# FMC_SINGLE_LPC_BREAKOUT.net
KiCad netlist of a schematic drawn in Altium Designer
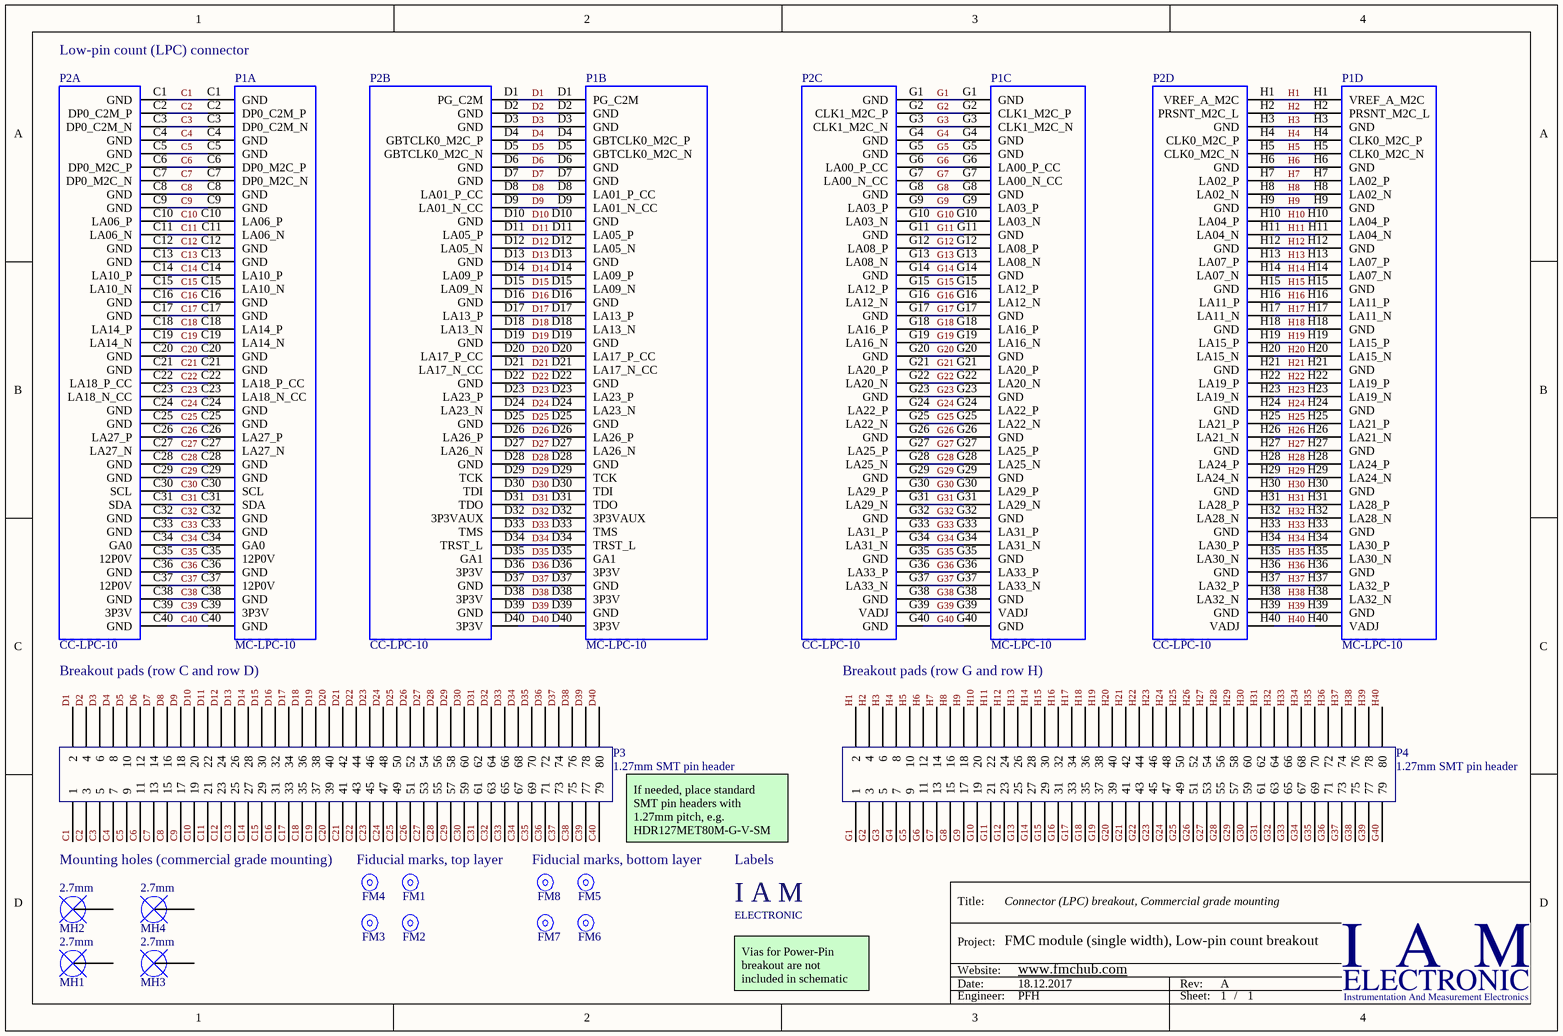
[diagram p0: FMC_SINGLE_LPC_BREAKOUT.SchDoc]

(export (version "E")
  (design (tool "Eeschema 10.0.6"))
  (components
    (comp (ref "FM1")
      (value "1mm")
      (footprint "FIDUCIAL_MARK_ROUND")
      (description "Fiducial mark, width 1mm, clearance 3mm")
      (libsource (lib "VITA_57_FMC") (part "Fiducial_Mark"))
    )
    (comp (ref "FM2")
      (value "1mm")
      (footprint "FIDUCIAL_MARK_ROUND")
      (description "Fiducial mark, width 1mm, clearance 3mm")
      (libsource (lib "VITA_57_FMC") (part "Fiducial_Mark"))
    )
    (comp (ref "FM3")
      (value "1mm")
      (footprint "FIDUCIAL_MARK_ROUND")
      (description "Fiducial mark, width 1mm, clearance 3mm")
      (libsource (lib "VITA_57_FMC") (part "Fiducial_Mark"))
    )
    (comp (ref "FM4")
      (value "1mm")
      (footprint "FIDUCIAL_MARK_ROUND")
      (description "Fiducial mark, width 1mm, clearance 3mm")
      (libsource (lib "VITA_57_FMC") (part "Fiducial_Mark"))
    )
    (comp (ref "FM5")
      (value "1mm")
      (footprint "FIDUCIAL_MARK_ROUND")
      (description "Fiducial mark, width 1mm, clearance 3mm")
      (libsource (lib "VITA_57_FMC") (part "Fiducial_Mark"))
    )
    (comp (ref "FM6")
      (value "1mm")
      (footprint "FIDUCIAL_MARK_ROUND")
      (description "Fiducial mark, width 1mm, clearance 3mm")
      (libsource (lib "VITA_57_FMC") (part "Fiducial_Mark"))
    )
    (comp (ref "FM7")
      (value "1mm")
      (footprint "FIDUCIAL_MARK_ROUND")
      (description "Fiducial mark, width 1mm, clearance 3mm")
      (libsource (lib "VITA_57_FMC") (part "Fiducial_Mark"))
    )
    (comp (ref "FM8")
      (value "1mm")
      (footprint "FIDUCIAL_MARK_ROUND")
      (description "Fiducial mark, width 1mm, clearance 3mm")
      (libsource (lib "VITA_57_FMC") (part "Fiducial_Mark"))
    )
    (comp (ref "MH1")
      (value "2.7mm")
      (footprint "Mounting_Hole_Plated_2.7mm - d3.1mm")
      (description "Mounting hole, hole size 2.7mm")
      (libsource (lib "VITA_57_FMC") (part "Mounting_Hole_2.7mm"))
    )
    (comp (ref "MH2")
      (value "2.7mm")
      (footprint "Mounting_Hole_Plated_2.7mm - d3.1mm")
      (description "Mounting hole, hole size 2.7mm")
      (libsource (lib "VITA_57_FMC") (part "Mounting_Hole_2.7mm"))
    )
    (comp (ref "MH3")
      (value "2.7mm")
      (footprint "Mounting_Hole_Plated_2.7mm-COVERED")
      (description "Mounting hole, hole size 2.7mm")
      (libsource (lib "VITA_57_FMC") (part "Mounting_Hole_2.7mm"))
    )
    (comp (ref "MH4")
      (value "2.7mm")
      (footprint "Mounting_Hole_Plated_2.7mm-COVERED")
      (description "Mounting hole, hole size 2.7mm")
      (libsource (lib "VITA_57_FMC") (part "Mounting_Hole_2.7mm"))
    )
    (comp (ref "P1")
      (value "MC-LPC-10")
      (footprint "ASP-134604-01")
      (description "MC-LPC-10, FMC Low-pin count connector, lead free, 160 I/Os, male, 10 mm mated stack height")
      (fields (field (name "MANUFACTURER") "Samtec") (field (name "PART") "ASP-134604-01"))
      (libsource (lib "VITA_57_FMC") (part "MC-LPC-10"))
    )
    (comp (ref "P2")
      (value "CC-LPC-10")
      (footprint "ASP-134603-01")
      (description "CC-LPC-10, FMC Low-pin count connector, lead free, 160 I/Os, female, 10 mm mated stack height")
      (fields (field (name "MANUFACTURER") "Samtec") (field (name "PART") "ASP-134603-01"))
      (libsource (lib "VITA_57_FMC") (part "CC-LPC-10"))
    )
    (comp (ref "P3")
      (value "1.27mm SMT pin header")
      (footprint "FTS-140-01-L-DV-A")
      (description "1.27 MM 80 PIN VERTICAL MALE HEADER")
      (fields (field (name "PART") "HDR127MET80M-G-V-SM") (field (name "MANUFACTURER") "Chip Quik Inc."))
      (libsource (lib "FTS-140") (part "FTS-140-X-DV"))
    )
    (comp (ref "P4")
      (value "1.27mm SMT pin header")
      (footprint "FTS-140-01-L-DV-A")
      (description "1.27 MM 80 PIN VERTICAL MALE HEADER")
      (fields (field (name "PART") "HDR127MET80M-G-V-SM") (field (name "MANUFACTURER") "Chip Quik Inc."))
      (libsource (lib "FTS-140") (part "FTS-140-X-DV"))
    )
    (comp (ref "STR1")
      (value "IAM LOGO")
      (footprint "IAM LOGO - MEDIUM")
      (description "I A M E L E C T R O N I C - Logo")
      (fields (field (name "MANUFACTURER") "IAM ELECTRONIC") (field (name "PART") "Logo"))
      (libsource (lib "IAM_LOGOS") (part "IAM_LOGO"))
    )
  )
  (nets
    (net (code "1") (name "/C1") (class "Default")
      (node (ref "P1") (pin "C1") (pinfunction "GND_C1") (pintype "passive"))
      (node (ref "P2") (pin "C1") (pinfunction "GND_C1") (pintype "passive"))
      (node (ref "P3") (pin "1") (pinfunction "1_1") (pintype "passive"))
    )
    (net (code "2") (name "/C2") (class "Default")
      (node (ref "P1") (pin "C2") (pinfunction "DP0_C2M_P_C2") (pintype "passive"))
      (node (ref "P2") (pin "C2") (pinfunction "DP0_C2M_P_C2") (pintype "passive"))
      (node (ref "P3") (pin "3") (pinfunction "3_3") (pintype "passive"))
    )
    (net (code "3") (name "/C3") (class "Default")
      (node (ref "P1") (pin "C3") (pinfunction "DP0_C2M_N_C3") (pintype "passive"))
      (node (ref "P2") (pin "C3") (pinfunction "DP0_C2M_N_C3") (pintype "passive"))
      (node (ref "P3") (pin "5") (pinfunction "5_5") (pintype "passive"))
    )
    (net (code "4") (name "/C4") (class "Default")
      (node (ref "P1") (pin "C4") (pinfunction "GND_C4") (pintype "passive"))
      (node (ref "P2") (pin "C4") (pinfunction "GND_C4") (pintype "passive"))
      (node (ref "P3") (pin "7") (pinfunction "7_7") (pintype "passive"))
    )
    (net (code "5") (name "/C5") (class "Default")
      (node (ref "P1") (pin "C5") (pinfunction "GND_C5") (pintype "passive"))
      (node (ref "P2") (pin "C5") (pinfunction "GND_C5") (pintype "passive"))
      (node (ref "P3") (pin "9") (pinfunction "9_9") (pintype "passive"))
    )
    (net (code "6") (name "/C6") (class "Default")
      (node (ref "P1") (pin "C6") (pinfunction "DP0_M2C_P_C6") (pintype "passive"))
      (node (ref "P2") (pin "C6") (pinfunction "DP0_M2C_P_C6") (pintype "passive"))
      (node (ref "P3") (pin "11") (pinfunction "11_11") (pintype "passive"))
    )
    (net (code "7") (name "/C7") (class "Default")
      (node (ref "P1") (pin "C7") (pinfunction "DP0_M2C_N_C7") (pintype "passive"))
      (node (ref "P2") (pin "C7") (pinfunction "DP0_M2C_N_C7") (pintype "passive"))
      (node (ref "P3") (pin "13") (pinfunction "13_13") (pintype "passive"))
    )
    (net (code "8") (name "/C8") (class "Default")
      (node (ref "P1") (pin "C8") (pinfunction "GND_C8") (pintype "passive"))
      (node (ref "P2") (pin "C8") (pinfunction "GND_C8") (pintype "passive"))
      (node (ref "P3") (pin "15") (pinfunction "15_15") (pintype "passive"))
    )
    (net (code "9") (name "/C9") (class "Default")
      (node (ref "P1") (pin "C9") (pinfunction "GND_C9") (pintype "passive"))
      (node (ref "P2") (pin "C9") (pinfunction "GND_C9") (pintype "passive"))
      (node (ref "P3") (pin "17") (pinfunction "17_17") (pintype "passive"))
    )
    (net (code "10") (name "/C10") (class "Default")
      (node (ref "P1") (pin "C10") (pinfunction "LA06_P_C10") (pintype "passive"))
      (node (ref "P2") (pin "C10") (pinfunction "LA06_P_C10") (pintype "passive"))
      (node (ref "P3") (pin "19") (pinfunction "19_19") (pintype "passive"))
    )
    (net (code "11") (name "/C11") (class "Default")
      (node (ref "P1") (pin "C11") (pinfunction "LA06_N_C11") (pintype "passive"))
      (node (ref "P2") (pin "C11") (pinfunction "LA06_N_C11") (pintype "passive"))
      (node (ref "P3") (pin "21") (pinfunction "21_21") (pintype "passive"))
    )
    (net (code "12") (name "/C12") (class "Default")
      (node (ref "P1") (pin "C12") (pinfunction "GND_C12") (pintype "passive"))
      (node (ref "P2") (pin "C12") (pinfunction "GND_C12") (pintype "passive"))
      (node (ref "P3") (pin "23") (pinfunction "23_23") (pintype "passive"))
    )
    (net (code "13") (name "/C13") (class "Default")
      (node (ref "P1") (pin "C13") (pinfunction "GND_C13") (pintype "passive"))
      (node (ref "P2") (pin "C13") (pinfunction "GND_C13") (pintype "passive"))
      (node (ref "P3") (pin "25") (pinfunction "25_25") (pintype "passive"))
    )
    (net (code "14") (name "/C14") (class "Default")
      (node (ref "P1") (pin "C14") (pinfunction "LA10_P_C14") (pintype "passive"))
      (node (ref "P2") (pin "C14") (pinfunction "LA10_P_C14") (pintype "passive"))
      (node (ref "P3") (pin "27") (pinfunction "27_27") (pintype "passive"))
    )
    (net (code "15") (name "/C15") (class "Default")
      (node (ref "P1") (pin "C15") (pinfunction "LA10_N_C15") (pintype "passive"))
      (node (ref "P2") (pin "C15") (pinfunction "LA10_N_C15") (pintype "passive"))
      (node (ref "P3") (pin "29") (pinfunction "29_29") (pintype "passive"))
    )
    (net (code "16") (name "/C16") (class "Default")
      (node (ref "P1") (pin "C16") (pinfunction "GND_C16") (pintype "passive"))
      (node (ref "P2") (pin "C16") (pinfunction "GND_C16") (pintype "passive"))
      (node (ref "P3") (pin "31") (pinfunction "31_31") (pintype "passive"))
    )
    (net (code "17") (name "/C17") (class "Default")
      (node (ref "P1") (pin "C17") (pinfunction "GND_C17") (pintype "passive"))
      (node (ref "P2") (pin "C17") (pinfunction "GND_C17") (pintype "passive"))
      (node (ref "P3") (pin "33") (pinfunction "33_33") (pintype "passive"))
    )
    (net (code "18") (name "/C18") (class "Default")
      (node (ref "P1") (pin "C18") (pinfunction "LA14_P_C18") (pintype "passive"))
      (node (ref "P2") (pin "C18") (pinfunction "LA14_P_C18") (pintype "passive"))
      (node (ref "P3") (pin "35") (pinfunction "35_35") (pintype "passive"))
    )
    (net (code "19") (name "/C19") (class "Default")
      (node (ref "P1") (pin "C19") (pinfunction "LA14_N_C19") (pintype "passive"))
      (node (ref "P2") (pin "C19") (pinfunction "LA14_N_C19") (pintype "passive"))
      (node (ref "P3") (pin "37") (pinfunction "37_37") (pintype "passive"))
    )
    (net (code "20") (name "/C20") (class "Default")
      (node (ref "P1") (pin "C20") (pinfunction "GND_C20") (pintype "passive"))
      (node (ref "P2") (pin "C20") (pinfunction "GND_C20") (pintype "passive"))
      (node (ref "P3") (pin "39") (pinfunction "39_39") (pintype "passive"))
    )
    (net (code "21") (name "/C21") (class "Default")
      (node (ref "P1") (pin "C21") (pinfunction "GND_C21") (pintype "passive"))
      (node (ref "P2") (pin "C21") (pinfunction "GND_C21") (pintype "passive"))
      (node (ref "P3") (pin "41") (pinfunction "41_41") (pintype "passive"))
    )
    (net (code "22") (name "/C22") (class "Default")
      (node (ref "P1") (pin "C22") (pinfunction "LA18_P_CC_C22") (pintype "passive"))
      (node (ref "P2") (pin "C22") (pinfunction "LA18_P_CC_C22") (pintype "passive"))
      (node (ref "P3") (pin "43") (pinfunction "43_43") (pintype "passive"))
    )
    (net (code "23") (name "/C23") (class "Default")
      (node (ref "P1") (pin "C23") (pinfunction "LA18_N_CC_C23") (pintype "passive"))
      (node (ref "P2") (pin "C23") (pinfunction "LA18_N_CC_C23") (pintype "passive"))
      (node (ref "P3") (pin "45") (pinfunction "45_45") (pintype "passive"))
    )
    (net (code "24") (name "/C24") (class "Default")
      (node (ref "P1") (pin "C24") (pinfunction "GND_C24") (pintype "passive"))
      (node (ref "P2") (pin "C24") (pinfunction "GND_C24") (pintype "passive"))
      (node (ref "P3") (pin "47") (pinfunction "47_47") (pintype "passive"))
    )
    (net (code "25") (name "/C25") (class "Default")
      (node (ref "P1") (pin "C25") (pinfunction "GND_C25") (pintype "passive"))
      (node (ref "P2") (pin "C25") (pinfunction "GND_C25") (pintype "passive"))
      (node (ref "P3") (pin "49") (pinfunction "49_49") (pintype "passive"))
    )
    (net (code "26") (name "/C26") (class "Default")
      (node (ref "P1") (pin "C26") (pinfunction "LA27_P_C26") (pintype "passive"))
      (node (ref "P2") (pin "C26") (pinfunction "LA27_P_C26") (pintype "passive"))
      (node (ref "P3") (pin "51") (pinfunction "51_51") (pintype "passive"))
    )
    (net (code "27") (name "/C27") (class "Default")
      (node (ref "P1") (pin "C27") (pinfunction "LA27_N_C27") (pintype "passive"))
      (node (ref "P2") (pin "C27") (pinfunction "LA27_N_C27") (pintype "passive"))
      (node (ref "P3") (pin "53") (pinfunction "53_53") (pintype "passive"))
    )
    (net (code "28") (name "/C28") (class "Default")
      (node (ref "P1") (pin "C28") (pinfunction "GND_C28") (pintype "passive"))
      (node (ref "P2") (pin "C28") (pinfunction "GND_C28") (pintype "passive"))
      (node (ref "P3") (pin "55") (pinfunction "55_55") (pintype "passive"))
    )
    (net (code "29") (name "/C29") (class "Default")
      (node (ref "P1") (pin "C29") (pinfunction "GND_C29") (pintype "passive"))
      (node (ref "P2") (pin "C29") (pinfunction "GND_C29") (pintype "passive"))
      (node (ref "P3") (pin "57") (pinfunction "57_57") (pintype "passive"))
    )
    (net (code "30") (name "/C30") (class "Default")
      (node (ref "P1") (pin "C30") (pinfunction "SCL_C30") (pintype "passive"))
      (node (ref "P2") (pin "C30") (pinfunction "SCL_C30") (pintype "passive"))
      (node (ref "P3") (pin "59") (pinfunction "59_59") (pintype "passive"))
    )
    (net (code "31") (name "/C31") (class "Default")
      (node (ref "P1") (pin "C31") (pinfunction "SDA_C31") (pintype "passive"))
      (node (ref "P2") (pin "C31") (pinfunction "SDA_C31") (pintype "passive"))
      (node (ref "P3") (pin "61") (pinfunction "61_61") (pintype "passive"))
    )
    (net (code "32") (name "/C32") (class "Default")
      (node (ref "P1") (pin "C32") (pinfunction "GND_C32") (pintype "passive"))
      (node (ref "P2") (pin "C32") (pinfunction "GND_C32") (pintype "passive"))
      (node (ref "P3") (pin "63") (pinfunction "63_63") (pintype "passive"))
    )
    (net (code "33") (name "/C33") (class "Default")
      (node (ref "P1") (pin "C33") (pinfunction "GND_C33") (pintype "passive"))
      (node (ref "P2") (pin "C33") (pinfunction "GND_C33") (pintype "passive"))
      (node (ref "P3") (pin "65") (pinfunction "65_65") (pintype "passive"))
    )
    (net (code "34") (name "/C34") (class "Default")
      (node (ref "P1") (pin "C34") (pinfunction "GA0_C34") (pintype "passive"))
      (node (ref "P2") (pin "C34") (pinfunction "GA0_C34") (pintype "passive"))
      (node (ref "P3") (pin "67") (pinfunction "67_67") (pintype "passive"))
    )
    (net (code "35") (name "/C35") (class "Default")
      (node (ref "P1") (pin "C35") (pinfunction "12P0V_C35") (pintype "passive"))
      (node (ref "P2") (pin "C35") (pinfunction "12P0V_C35") (pintype "passive"))
      (node (ref "P3") (pin "69") (pinfunction "69_69") (pintype "passive"))
    )
    (net (code "36") (name "/C36") (class "Default")
      (node (ref "P1") (pin "C36") (pinfunction "GND_C36") (pintype "passive"))
      (node (ref "P2") (pin "C36") (pinfunction "GND_C36") (pintype "passive"))
      (node (ref "P3") (pin "71") (pinfunction "71_71") (pintype "passive"))
    )
    (net (code "37") (name "/C37") (class "Default")
      (node (ref "P1") (pin "C37") (pinfunction "12P0V_C37") (pintype "passive"))
      (node (ref "P2") (pin "C37") (pinfunction "12P0V_C37") (pintype "passive"))
      (node (ref "P3") (pin "73") (pinfunction "73_73") (pintype "passive"))
    )
    (net (code "38") (name "/C38") (class "Default")
      (node (ref "P1") (pin "C38") (pinfunction "GND_C38") (pintype "passive"))
      (node (ref "P2") (pin "C38") (pinfunction "GND_C38") (pintype "passive"))
      (node (ref "P3") (pin "75") (pinfunction "75_75") (pintype "passive"))
    )
    (net (code "39") (name "/C39") (class "Default")
      (node (ref "P1") (pin "C39") (pinfunction "3P3V_C39") (pintype "passive"))
      (node (ref "P2") (pin "C39") (pinfunction "3P3V_C39") (pintype "passive"))
      (node (ref "P3") (pin "77") (pinfunction "77_77") (pintype "passive"))
    )
    (net (code "40") (name "/C40") (class "Default")
      (node (ref "P1") (pin "C40") (pinfunction "GND_C40") (pintype "passive"))
      (node (ref "P2") (pin "C40") (pinfunction "GND_C40") (pintype "passive"))
      (node (ref "P3") (pin "79") (pinfunction "79_79") (pintype "passive"))
    )
    (net (code "41") (name "/D1") (class "Default")
      (node (ref "P1") (pin "D1") (pinfunction "PG_C2M_D1") (pintype "passive"))
      (node (ref "P2") (pin "D1") (pinfunction "PG_C2M_D1") (pintype "passive"))
      (node (ref "P3") (pin "2") (pinfunction "2_2") (pintype "passive"))
    )
    (net (code "42") (name "/D2") (class "Default")
      (node (ref "P1") (pin "D2") (pinfunction "GND_D2") (pintype "passive"))
      (node (ref "P2") (pin "D2") (pinfunction "GND_D2") (pintype "passive"))
      (node (ref "P3") (pin "4") (pinfunction "4_4") (pintype "passive"))
    )
    (net (code "43") (name "/D3") (class "Default")
      (node (ref "P1") (pin "D3") (pinfunction "GND_D3") (pintype "passive"))
      (node (ref "P2") (pin "D3") (pinfunction "GND_D3") (pintype "passive"))
      (node (ref "P3") (pin "6") (pinfunction "6_6") (pintype "passive"))
    )
    (net (code "44") (name "/D4") (class "Default")
      (node (ref "P1") (pin "D4") (pinfunction "GBTCLK0_M2C_P_D4") (pintype "passive"))
      (node (ref "P2") (pin "D4") (pinfunction "GBTCLK0_M2C_P_D4") (pintype "passive"))
      (node (ref "P3") (pin "8") (pinfunction "8_8") (pintype "passive"))
    )
    (net (code "45") (name "/D5") (class "Default")
      (node (ref "P1") (pin "D5") (pinfunction "GBTCLK0_M2C_N_D5") (pintype "passive"))
      (node (ref "P2") (pin "D5") (pinfunction "GBTCLK0_M2C_N_D5") (pintype "passive"))
      (node (ref "P3") (pin "10") (pinfunction "10_10") (pintype "passive"))
    )
    (net (code "46") (name "/D6") (class "Default")
      (node (ref "P1") (pin "D6") (pinfunction "GND_D6") (pintype "passive"))
      (node (ref "P2") (pin "D6") (pinfunction "GND_D6") (pintype "passive"))
      (node (ref "P3") (pin "12") (pinfunction "12_12") (pintype "passive"))
    )
    (net (code "47") (name "/D7") (class "Default")
      (node (ref "P1") (pin "D7") (pinfunction "GND_D7") (pintype "passive"))
      (node (ref "P2") (pin "D7") (pinfunction "GND_D7") (pintype "passive"))
      (node (ref "P3") (pin "14") (pinfunction "14_14") (pintype "passive"))
    )
    (net (code "48") (name "/D8") (class "Default")
      (node (ref "P1") (pin "D8") (pinfunction "LA01_P_CC_D8") (pintype "passive"))
      (node (ref "P2") (pin "D8") (pinfunction "LA01_P_CC_D8") (pintype "passive"))
      (node (ref "P3") (pin "16") (pinfunction "16_16") (pintype "passive"))
    )
    (net (code "49") (name "/D9") (class "Default")
      (node (ref "P1") (pin "D9") (pinfunction "LA01_N_CC_D9") (pintype "passive"))
      (node (ref "P2") (pin "D9") (pinfunction "LA01_N_CC_D9") (pintype "passive"))
      (node (ref "P3") (pin "18") (pinfunction "18_18") (pintype "passive"))
    )
    (net (code "50") (name "/D10") (class "Default")
      (node (ref "P1") (pin "D10") (pinfunction "GND_D10") (pintype "passive"))
      (node (ref "P2") (pin "D10") (pinfunction "GND_D10") (pintype "passive"))
      (node (ref "P3") (pin "20") (pinfunction "20_20") (pintype "passive"))
    )
    (net (code "51") (name "/D11") (class "Default")
      (node (ref "P1") (pin "D11") (pinfunction "LA05_P_D11") (pintype "passive"))
      (node (ref "P2") (pin "D11") (pinfunction "LA05_P_D11") (pintype "passive"))
      (node (ref "P3") (pin "22") (pinfunction "22_22") (pintype "passive"))
    )
    (net (code "52") (name "/D12") (class "Default")
      (node (ref "P1") (pin "D12") (pinfunction "LA05_N_D12") (pintype "passive"))
      (node (ref "P2") (pin "D12") (pinfunction "LA05_N_D12") (pintype "passive"))
      (node (ref "P3") (pin "24") (pinfunction "24_24") (pintype "passive"))
    )
    (net (code "53") (name "/D13") (class "Default")
      (node (ref "P1") (pin "D13") (pinfunction "GND_D13") (pintype "passive"))
      (node (ref "P2") (pin "D13") (pinfunction "GND_D13") (pintype "passive"))
      (node (ref "P3") (pin "26") (pinfunction "26_26") (pintype "passive"))
    )
    (net (code "54") (name "/D14") (class "Default")
      (node (ref "P1") (pin "D14") (pinfunction "LA09_P_D14") (pintype "passive"))
      (node (ref "P2") (pin "D14") (pinfunction "LA09_P_D14") (pintype "passive"))
      (node (ref "P3") (pin "28") (pinfunction "28_28") (pintype "passive"))
    )
    (net (code "55") (name "/D15") (class "Default")
      (node (ref "P1") (pin "D15") (pinfunction "LA09_N_D15") (pintype "passive"))
      (node (ref "P2") (pin "D15") (pinfunction "LA09_N_D15") (pintype "passive"))
      (node (ref "P3") (pin "30") (pinfunction "30_30") (pintype "passive"))
    )
    (net (code "56") (name "/D16") (class "Default")
      (node (ref "P1") (pin "D16") (pinfunction "GND_D16") (pintype "passive"))
      (node (ref "P2") (pin "D16") (pinfunction "GND_D16") (pintype "passive"))
      (node (ref "P3") (pin "32") (pinfunction "32_32") (pintype "passive"))
    )
    (net (code "57") (name "/D17") (class "Default")
      (node (ref "P1") (pin "D17") (pinfunction "LA13_P_D17") (pintype "passive"))
      (node (ref "P2") (pin "D17") (pinfunction "LA13_P_D17") (pintype "passive"))
      (node (ref "P3") (pin "34") (pinfunction "34_34") (pintype "passive"))
    )
    (net (code "58") (name "/D18") (class "Default")
      (node (ref "P1") (pin "D18") (pinfunction "LA13_N_D18") (pintype "passive"))
      (node (ref "P2") (pin "D18") (pinfunction "LA13_N_D18") (pintype "passive"))
      (node (ref "P3") (pin "36") (pinfunction "36_36") (pintype "passive"))
    )
    (net (code "59") (name "/D19") (class "Default")
      (node (ref "P1") (pin "D19") (pinfunction "GND_D19") (pintype "passive"))
      (node (ref "P2") (pin "D19") (pinfunction "GND_D19") (pintype "passive"))
      (node (ref "P3") (pin "38") (pinfunction "38_38") (pintype "passive"))
    )
    (net (code "60") (name "/D20") (class "Default")
      (node (ref "P1") (pin "D20") (pinfunction "LA17_P_CC_D20") (pintype "passive"))
      (node (ref "P2") (pin "D20") (pinfunction "LA17_P_CC_D20") (pintype "passive"))
      (node (ref "P3") (pin "40") (pinfunction "40_40") (pintype "passive"))
    )
    (net (code "61") (name "/D21") (class "Default")
      (node (ref "P1") (pin "D21") (pinfunction "LA17_N_CC_D21") (pintype "passive"))
      (node (ref "P2") (pin "D21") (pinfunction "LA17_N_CC_D21") (pintype "passive"))
      (node (ref "P3") (pin "42") (pinfunction "42_42") (pintype "passive"))
    )
    (net (code "62") (name "/D22") (class "Default")
      (node (ref "P1") (pin "D22") (pinfunction "GND_D22") (pintype "passive"))
      (node (ref "P2") (pin "D22") (pinfunction "GND_D22") (pintype "passive"))
      (node (ref "P3") (pin "44") (pinfunction "44_44") (pintype "passive"))
    )
    (net (code "63") (name "/D23") (class "Default")
      (node (ref "P1") (pin "D23") (pinfunction "LA23_P_D23") (pintype "passive"))
      (node (ref "P2") (pin "D23") (pinfunction "LA23_P_D23") (pintype "passive"))
      (node (ref "P3") (pin "46") (pinfunction "46_46") (pintype "passive"))
    )
    (net (code "64") (name "/D24") (class "Default")
      (node (ref "P1") (pin "D24") (pinfunction "LA23_N_D24") (pintype "passive"))
      (node (ref "P2") (pin "D24") (pinfunction "LA23_N_D24") (pintype "passive"))
      (node (ref "P3") (pin "48") (pinfunction "48_48") (pintype "passive"))
    )
    (net (code "65") (name "/D25") (class "Default")
      (node (ref "P1") (pin "D25") (pinfunction "GND_D25") (pintype "passive"))
      (node (ref "P2") (pin "D25") (pinfunction "GND_D25") (pintype "passive"))
      (node (ref "P3") (pin "50") (pinfunction "50_50") (pintype "passive"))
    )
    (net (code "66") (name "/D26") (class "Default")
      (node (ref "P1") (pin "D26") (pinfunction "LA26_P_D26") (pintype "passive"))
      (node (ref "P2") (pin "D26") (pinfunction "LA26_P_D26") (pintype "passive"))
      (node (ref "P3") (pin "52") (pinfunction "52_52") (pintype "passive"))
    )
    (net (code "67") (name "/D27") (class "Default")
      (node (ref "P1") (pin "D27") (pinfunction "LA26_N_D27") (pintype "passive"))
      (node (ref "P2") (pin "D27") (pinfunction "LA26_N_D27") (pintype "passive"))
      (node (ref "P3") (pin "54") (pinfunction "54_54") (pintype "passive"))
    )
    (net (code "68") (name "/D28") (class "Default")
      (node (ref "P1") (pin "D28") (pinfunction "GND_D28") (pintype "passive"))
      (node (ref "P2") (pin "D28") (pinfunction "GND_D28") (pintype "passive"))
      (node (ref "P3") (pin "56") (pinfunction "56_56") (pintype "passive"))
    )
    (net (code "69") (name "/D29") (class "Default")
      (node (ref "P1") (pin "D29") (pinfunction "TCK_D29") (pintype "passive"))
      (node (ref "P2") (pin "D29") (pinfunction "TCK_D29") (pintype "passive"))
      (node (ref "P3") (pin "58") (pinfunction "58_58") (pintype "passive"))
    )
    (net (code "70") (name "/D30") (class "Default")
      (node (ref "P1") (pin "D30") (pinfunction "TDI_D30") (pintype "passive"))
      (node (ref "P2") (pin "D30") (pinfunction "TDI_D30") (pintype "passive"))
      (node (ref "P3") (pin "60") (pinfunction "60_60") (pintype "passive"))
    )
    (net (code "71") (name "/D31") (class "Default")
      (node (ref "P1") (pin "D31") (pinfunction "TDO_D31") (pintype "passive"))
      (node (ref "P2") (pin "D31") (pinfunction "TDO_D31") (pintype "passive"))
      (node (ref "P3") (pin "62") (pinfunction "62_62") (pintype "passive"))
    )
    (net (code "72") (name "/D32") (class "Default")
      (node (ref "P1") (pin "D32") (pinfunction "3P3VAUX_D32") (pintype "passive"))
      (node (ref "P2") (pin "D32") (pinfunction "3P3VAUX_D32") (pintype "passive"))
      (node (ref "P3") (pin "64") (pinfunction "64_64") (pintype "passive"))
    )
    (net (code "73") (name "/D33") (class "Default")
      (node (ref "P1") (pin "D33") (pinfunction "TMS_D33") (pintype "passive"))
      (node (ref "P2") (pin "D33") (pinfunction "TMS_D33") (pintype "passive"))
      (node (ref "P3") (pin "66") (pinfunction "66_66") (pintype "passive"))
    )
    (net (code "74") (name "/D34") (class "Default")
      (node (ref "P1") (pin "D34") (pinfunction "TRST_L_D34") (pintype "passive"))
      (node (ref "P2") (pin "D34") (pinfunction "TRST_L_D34") (pintype "passive"))
      (node (ref "P3") (pin "68") (pinfunction "68_68") (pintype "passive"))
    )
    (net (code "75") (name "/D35") (class "Default")
      (node (ref "P1") (pin "D35") (pinfunction "GA1_D35") (pintype "passive"))
      (node (ref "P2") (pin "D35") (pinfunction "GA1_D35") (pintype "passive"))
      (node (ref "P3") (pin "70") (pinfunction "70_70") (pintype "passive"))
    )
    (net (code "76") (name "/D36") (class "Default")
      (node (ref "P1") (pin "D36") (pinfunction "3P3V_D36") (pintype "passive"))
      (node (ref "P2") (pin "D36") (pinfunction "3P3V_D36") (pintype "passive"))
      (node (ref "P3") (pin "72") (pinfunction "72_72") (pintype "passive"))
    )
    (net (code "77") (name "/D37") (class "Default")
      (node (ref "P1") (pin "D37") (pinfunction "GND_D37") (pintype "passive"))
      (node (ref "P2") (pin "D37") (pinfunction "GND_D37") (pintype "passive"))
      (node (ref "P3") (pin "74") (pinfunction "74_74") (pintype "passive"))
    )
    (net (code "78") (name "/D38") (class "Default")
      (node (ref "P1") (pin "D38") (pinfunction "3P3V_D38") (pintype "passive"))
      (node (ref "P2") (pin "D38") (pinfunction "3P3V_D38") (pintype "passive"))
      (node (ref "P3") (pin "76") (pinfunction "76_76") (pintype "passive"))
    )
    (net (code "79") (name "/D39") (class "Default")
      (node (ref "P1") (pin "D39") (pinfunction "GND_D39") (pintype "passive"))
      (node (ref "P2") (pin "D39") (pinfunction "GND_D39") (pintype "passive"))
      (node (ref "P3") (pin "78") (pinfunction "78_78") (pintype "passive"))
    )
    (net (code "80") (name "/D40") (class "Default")
      (node (ref "P1") (pin "D40") (pinfunction "3P3V_D40") (pintype "passive"))
      (node (ref "P2") (pin "D40") (pinfunction "3P3V_D40") (pintype "passive"))
      (node (ref "P3") (pin "80") (pinfunction "80_80") (pintype "passive"))
    )
    (net (code "81") (name "/G1") (class "Default")
      (node (ref "P1") (pin "G1") (pinfunction "GND_G1") (pintype "passive"))
      (node (ref "P2") (pin "G1") (pinfunction "GND_G1") (pintype "passive"))
      (node (ref "P4") (pin "1") (pinfunction "1_1") (pintype "passive"))
    )
    (net (code "82") (name "/G2") (class "Default")
      (node (ref "P1") (pin "G2") (pinfunction "CLK1_M2C_P_G2") (pintype "passive"))
      (node (ref "P2") (pin "G2") (pinfunction "CLK1_M2C_P_G2") (pintype "passive"))
      (node (ref "P4") (pin "3") (pinfunction "3_3") (pintype "passive"))
    )
    (net (code "83") (name "/G3") (class "Default")
      (node (ref "P1") (pin "G3") (pinfunction "CLK1_M2C_N_G3") (pintype "passive"))
      (node (ref "P2") (pin "G3") (pinfunction "CLK1_M2C_N_G3") (pintype "passive"))
      (node (ref "P4") (pin "5") (pinfunction "5_5") (pintype "passive"))
    )
    (net (code "84") (name "/G4") (class "Default")
      (node (ref "P1") (pin "G4") (pinfunction "GND_G4") (pintype "passive"))
      (node (ref "P2") (pin "G4") (pinfunction "GND_G4") (pintype "passive"))
      (node (ref "P4") (pin "7") (pinfunction "7_7") (pintype "passive"))
    )
    (net (code "85") (name "/G5") (class "Default")
      (node (ref "P1") (pin "G5") (pinfunction "GND_G5") (pintype "passive"))
      (node (ref "P2") (pin "G5") (pinfunction "GND_G5") (pintype "passive"))
      (node (ref "P4") (pin "9") (pinfunction "9_9") (pintype "passive"))
    )
    (net (code "86") (name "/G6") (class "Default")
      (node (ref "P1") (pin "G6") (pinfunction "LA00_P_CC_G6") (pintype "passive"))
      (node (ref "P2") (pin "G6") (pinfunction "LA00_P_CC_G6") (pintype "passive"))
      (node (ref "P4") (pin "11") (pinfunction "11_11") (pintype "passive"))
    )
    (net (code "87") (name "/G7") (class "Default")
      (node (ref "P1") (pin "G7") (pinfunction "LA00_N_CC_G7") (pintype "passive"))
      (node (ref "P2") (pin "G7") (pinfunction "LA00_N_CC_G7") (pintype "passive"))
      (node (ref "P4") (pin "13") (pinfunction "13_13") (pintype "passive"))
    )
    (net (code "88") (name "/G8") (class "Default")
      (node (ref "P1") (pin "G8") (pinfunction "GND_G8") (pintype "passive"))
      (node (ref "P2") (pin "G8") (pinfunction "GND_G8") (pintype "passive"))
      (node (ref "P4") (pin "15") (pinfunction "15_15") (pintype "passive"))
    )
    (net (code "89") (name "/G9") (class "Default")
      (node (ref "P1") (pin "G9") (pinfunction "LA03_P_G9") (pintype "passive"))
      (node (ref "P2") (pin "G9") (pinfunction "LA03_P_G9") (pintype "passive"))
      (node (ref "P4") (pin "17") (pinfunction "17_17") (pintype "passive"))
    )
    (net (code "90") (name "/G10") (class "Default")
      (node (ref "P1") (pin "G10") (pinfunction "LA03_N_G10") (pintype "passive"))
      (node (ref "P2") (pin "G10") (pinfunction "LA03_N_G10") (pintype "passive"))
      (node (ref "P4") (pin "19") (pinfunction "19_19") (pintype "passive"))
    )
    (net (code "91") (name "/G11") (class "Default")
      (node (ref "P1") (pin "G11") (pinfunction "GND_G11") (pintype "passive"))
      (node (ref "P2") (pin "G11") (pinfunction "GND_G11") (pintype "passive"))
      (node (ref "P4") (pin "21") (pinfunction "21_21") (pintype "passive"))
    )
    (net (code "92") (name "/G12") (class "Default")
      (node (ref "P1") (pin "G12") (pinfunction "LA08_P_G12") (pintype "passive"))
      (node (ref "P2") (pin "G12") (pinfunction "LA08_P_G12") (pintype "passive"))
      (node (ref "P4") (pin "23") (pinfunction "23_23") (pintype "passive"))
    )
    (net (code "93") (name "/G13") (class "Default")
      (node (ref "P1") (pin "G13") (pinfunction "LA08_N_G13") (pintype "passive"))
      (node (ref "P2") (pin "G13") (pinfunction "LA08_N_G13") (pintype "passive"))
      (node (ref "P4") (pin "25") (pinfunction "25_25") (pintype "passive"))
    )
    (net (code "94") (name "/G14") (class "Default")
      (node (ref "P1") (pin "G14") (pinfunction "GND_G14") (pintype "passive"))
      (node (ref "P2") (pin "G14") (pinfunction "GND_G14") (pintype "passive"))
      (node (ref "P4") (pin "27") (pinfunction "27_27") (pintype "passive"))
    )
    (net (code "95") (name "/G15") (class "Default")
      (node (ref "P1") (pin "G15") (pinfunction "LA12_P_G15") (pintype "passive"))
      (node (ref "P2") (pin "G15") (pinfunction "LA12_P_G15") (pintype "passive"))
      (node (ref "P4") (pin "29") (pinfunction "29_29") (pintype "passive"))
    )
    (net (code "96") (name "/G16") (class "Default")
      (node (ref "P1") (pin "G16") (pinfunction "LA12_N_G16") (pintype "passive"))
      (node (ref "P2") (pin "G16") (pinfunction "LA12_N_G16") (pintype "passive"))
      (node (ref "P4") (pin "31") (pinfunction "31_31") (pintype "passive"))
    )
    (net (code "97") (name "/G17") (class "Default")
      (node (ref "P1") (pin "G17") (pinfunction "GND_G17") (pintype "passive"))
      (node (ref "P2") (pin "G17") (pinfunction "GND_G17") (pintype "passive"))
      (node (ref "P4") (pin "33") (pinfunction "33_33") (pintype "passive"))
    )
    (net (code "98") (name "/G18") (class "Default")
      (node (ref "P1") (pin "G18") (pinfunction "LA16_P_G18") (pintype "passive"))
      (node (ref "P2") (pin "G18") (pinfunction "LA16_P_G18") (pintype "passive"))
      (node (ref "P4") (pin "35") (pinfunction "35_35") (pintype "passive"))
    )
    (net (code "99") (name "/G19") (class "Default")
      (node (ref "P1") (pin "G19") (pinfunction "LA16_N_G19") (pintype "passive"))
      (node (ref "P2") (pin "G19") (pinfunction "LA16_N_G19") (pintype "passive"))
      (node (ref "P4") (pin "37") (pinfunction "37_37") (pintype "passive"))
    )
    (net (code "100") (name "/G20") (class "Default")
      (node (ref "P1") (pin "G20") (pinfunction "GND_G20") (pintype "passive"))
      (node (ref "P2") (pin "G20") (pinfunction "GND_G20") (pintype "passive"))
      (node (ref "P4") (pin "39") (pinfunction "39_39") (pintype "passive"))
    )
    (net (code "101") (name "/G21") (class "Default")
      (node (ref "P1") (pin "G21") (pinfunction "LA20_P_G21") (pintype "passive"))
      (node (ref "P2") (pin "G21") (pinfunction "LA20_P_G21") (pintype "passive"))
      (node (ref "P4") (pin "41") (pinfunction "41_41") (pintype "passive"))
    )
    (net (code "102") (name "/G22") (class "Default")
      (node (ref "P1") (pin "G22") (pinfunction "LA20_N_G22") (pintype "passive"))
      (node (ref "P2") (pin "G22") (pinfunction "LA20_N_G22") (pintype "passive"))
      (node (ref "P4") (pin "43") (pinfunction "43_43") (pintype "passive"))
    )
    (net (code "103") (name "/G23") (class "Default")
      (node (ref "P1") (pin "G23") (pinfunction "GND_G23") (pintype "passive"))
      (node (ref "P2") (pin "G23") (pinfunction "GND_G23") (pintype "passive"))
      (node (ref "P4") (pin "45") (pinfunction "45_45") (pintype "passive"))
    )
    (net (code "104") (name "/G24") (class "Default")
      (node (ref "P1") (pin "G24") (pinfunction "LA22_P_G24") (pintype "passive"))
      (node (ref "P2") (pin "G24") (pinfunction "LA22_P_G24") (pintype "passive"))
      (node (ref "P4") (pin "47") (pinfunction "47_47") (pintype "passive"))
    )
    (net (code "105") (name "/G25") (class "Default")
      (node (ref "P1") (pin "G25") (pinfunction "LA22_N_G25") (pintype "passive"))
      (node (ref "P2") (pin "G25") (pinfunction "LA22_N_G25") (pintype "passive"))
      (node (ref "P4") (pin "49") (pinfunction "49_49") (pintype "passive"))
    )
    (net (code "106") (name "/G26") (class "Default")
      (node (ref "P1") (pin "G26") (pinfunction "GND_G26") (pintype "passive"))
      (node (ref "P2") (pin "G26") (pinfunction "GND_G26") (pintype "passive"))
      (node (ref "P4") (pin "51") (pinfunction "51_51") (pintype "passive"))
    )
    (net (code "107") (name "/G27") (class "Default")
      (node (ref "P1") (pin "G27") (pinfunction "LA25_P_G27") (pintype "passive"))
      (node (ref "P2") (pin "G27") (pinfunction "LA25_P_G27") (pintype "passive"))
      (node (ref "P4") (pin "53") (pinfunction "53_53") (pintype "passive"))
    )
    (net (code "108") (name "/G28") (class "Default")
      (node (ref "P1") (pin "G28") (pinfunction "LA25_N_G28") (pintype "passive"))
      (node (ref "P2") (pin "G28") (pinfunction "LA25_N_G28") (pintype "passive"))
      (node (ref "P4") (pin "55") (pinfunction "55_55") (pintype "passive"))
    )
    (net (code "109") (name "/G29") (class "Default")
      (node (ref "P1") (pin "G29") (pinfunction "GND_G29") (pintype "passive"))
      (node (ref "P2") (pin "G29") (pinfunction "GND_G29") (pintype "passive"))
      (node (ref "P4") (pin "57") (pinfunction "57_57") (pintype "passive"))
    )
    (net (code "110") (name "/G30") (class "Default")
      (node (ref "P1") (pin "G30") (pinfunction "LA29_P_G30") (pintype "passive"))
      (node (ref "P2") (pin "G30") (pinfunction "LA29_P_G30") (pintype "passive"))
      (node (ref "P4") (pin "59") (pinfunction "59_59") (pintype "passive"))
    )
    (net (code "111") (name "/G31") (class "Default")
      (node (ref "P1") (pin "G31") (pinfunction "LA29_N_G31") (pintype "passive"))
      (node (ref "P2") (pin "G31") (pinfunction "LA29_N_G31") (pintype "passive"))
      (node (ref "P4") (pin "61") (pinfunction "61_61") (pintype "passive"))
    )
    (net (code "112") (name "/G32") (class "Default")
      (node (ref "P1") (pin "G32") (pinfunction "GND_G32") (pintype "passive"))
      (node (ref "P2") (pin "G32") (pinfunction "GND_G32") (pintype "passive"))
      (node (ref "P4") (pin "63") (pinfunction "63_63") (pintype "passive"))
    )
    (net (code "113") (name "/G33") (class "Default")
      (node (ref "P1") (pin "G33") (pinfunction "LA31_P_G33") (pintype "passive"))
      (node (ref "P2") (pin "G33") (pinfunction "LA31_P_G33") (pintype "passive"))
      (node (ref "P4") (pin "65") (pinfunction "65_65") (pintype "passive"))
    )
    (net (code "114") (name "/G34") (class "Default")
      (node (ref "P1") (pin "G34") (pinfunction "LA31_N_G34") (pintype "passive"))
      (node (ref "P2") (pin "G34") (pinfunction "LA31_N_G34") (pintype "passive"))
      (node (ref "P4") (pin "67") (pinfunction "67_67") (pintype "passive"))
    )
    (net (code "115") (name "/G35") (class "Default")
      (node (ref "P1") (pin "G35") (pinfunction "GND_G35") (pintype "passive"))
      (node (ref "P2") (pin "G35") (pinfunction "GND_G35") (pintype "passive"))
      (node (ref "P4") (pin "69") (pinfunction "69_69") (pintype "passive"))
    )
    (net (code "116") (name "/G36") (class "Default")
      (node (ref "P1") (pin "G36") (pinfunction "LA33_P_G36") (pintype "passive"))
      (node (ref "P2") (pin "G36") (pinfunction "LA33_P_G36") (pintype "passive"))
      (node (ref "P4") (pin "71") (pinfunction "71_71") (pintype "passive"))
    )
    (net (code "117") (name "/G37") (class "Default")
      (node (ref "P1") (pin "G37") (pinfunction "LA33_N_G37") (pintype "passive"))
      (node (ref "P2") (pin "G37") (pinfunction "LA33_N_G37") (pintype "passive"))
      (node (ref "P4") (pin "73") (pinfunction "73_73") (pintype "passive"))
    )
    (net (code "118") (name "/G38") (class "Default")
      (node (ref "P1") (pin "G38") (pinfunction "GND_G38") (pintype "passive"))
      (node (ref "P2") (pin "G38") (pinfunction "GND_G38") (pintype "passive"))
      (node (ref "P4") (pin "75") (pinfunction "75_75") (pintype "passive"))
    )
    (net (code "119") (name "/G39") (class "Default")
      (node (ref "P1") (pin "G39") (pinfunction "VADJ_G39") (pintype "passive"))
      (node (ref "P2") (pin "G39") (pinfunction "VADJ_G39") (pintype "passive"))
      (node (ref "P4") (pin "77") (pinfunction "77_77") (pintype "passive"))
    )
    (net (code "120") (name "/G40") (class "Default")
      (node (ref "P1") (pin "G40") (pinfunction "GND_G40") (pintype "passive"))
      (node (ref "P2") (pin "G40") (pinfunction "GND_G40") (pintype "passive"))
      (node (ref "P4") (pin "79") (pinfunction "79_79") (pintype "passive"))
    )
    (net (code "121") (name "/H1") (class "Default")
      (node (ref "P1") (pin "H1") (pinfunction "VREF_A_M2C_H1") (pintype "passive"))
      (node (ref "P2") (pin "H1") (pinfunction "VREF_A_M2C_H1") (pintype "passive"))
      (node (ref "P4") (pin "2") (pinfunction "2_2") (pintype "passive"))
    )
    (net (code "122") (name "/H2") (class "Default")
      (node (ref "P1") (pin "H2") (pinfunction "PRSNT_M2C_L_H2") (pintype "passive"))
      (node (ref "P2") (pin "H2") (pinfunction "PRSNT_M2C_L_H2") (pintype "passive"))
      (node (ref "P4") (pin "4") (pinfunction "4_4") (pintype "passive"))
    )
    (net (code "123") (name "/H3") (class "Default")
      (node (ref "P1") (pin "H3") (pinfunction "GND_H3") (pintype "passive"))
      (node (ref "P2") (pin "H3") (pinfunction "GND_H3") (pintype "passive"))
      (node (ref "P4") (pin "6") (pinfunction "6_6") (pintype "passive"))
    )
    (net (code "124") (name "/H4") (class "Default")
      (node (ref "P1") (pin "H4") (pinfunction "CLK0_M2C_P_H4") (pintype "passive"))
      (node (ref "P2") (pin "H4") (pinfunction "CLK0_M2C_P_H4") (pintype "passive"))
      (node (ref "P4") (pin "8") (pinfunction "8_8") (pintype "passive"))
    )
    (net (code "125") (name "/H5") (class "Default")
      (node (ref "P1") (pin "H5") (pinfunction "CLK0_M2C_N_H5") (pintype "passive"))
      (node (ref "P2") (pin "H5") (pinfunction "CLK0_M2C_N_H5") (pintype "passive"))
      (node (ref "P4") (pin "10") (pinfunction "10_10") (pintype "passive"))
    )
    (net (code "126") (name "/H6") (class "Default")
      (node (ref "P1") (pin "H6") (pinfunction "GND_H6") (pintype "passive"))
      (node (ref "P2") (pin "H6") (pinfunction "GND_H6") (pintype "passive"))
      (node (ref "P4") (pin "12") (pinfunction "12_12") (pintype "passive"))
    )
    (net (code "127") (name "/H7") (class "Default")
      (node (ref "P1") (pin "H7") (pinfunction "LA02_P_H7") (pintype "passive"))
      (node (ref "P2") (pin "H7") (pinfunction "LA02_P_H7") (pintype "passive"))
      (node (ref "P4") (pin "14") (pinfunction "14_14") (pintype "passive"))
    )
    (net (code "128") (name "/H8") (class "Default")
      (node (ref "P1") (pin "H8") (pinfunction "LA02_N_H8") (pintype "passive"))
      (node (ref "P2") (pin "H8") (pinfunction "LA02_N_H8") (pintype "passive"))
      (node (ref "P4") (pin "16") (pinfunction "16_16") (pintype "passive"))
    )
    (net (code "129") (name "/H9") (class "Default")
      (node (ref "P1") (pin "H9") (pinfunction "GND_H9") (pintype "passive"))
      (node (ref "P2") (pin "H9") (pinfunction "GND_H9") (pintype "passive"))
      (node (ref "P4") (pin "18") (pinfunction "18_18") (pintype "passive"))
    )
    (net (code "130") (name "/H10") (class "Default")
      (node (ref "P1") (pin "H10") (pinfunction "LA04_P_H10") (pintype "passive"))
      (node (ref "P2") (pin "H10") (pinfunction "LA04_P_H10") (pintype "passive"))
      (node (ref "P4") (pin "20") (pinfunction "20_20") (pintype "passive"))
    )
    (net (code "131") (name "/H11") (class "Default")
      (node (ref "P1") (pin "H11") (pinfunction "LA04_N_H11") (pintype "passive"))
      (node (ref "P2") (pin "H11") (pinfunction "LA04_N_H11") (pintype "passive"))
      (node (ref "P4") (pin "22") (pinfunction "22_22") (pintype "passive"))
    )
    (net (code "132") (name "/H12") (class "Default")
      (node (ref "P1") (pin "H12") (pinfunction "GND_H12") (pintype "passive"))
      (node (ref "P2") (pin "H12") (pinfunction "GND_H12") (pintype "passive"))
      (node (ref "P4") (pin "24") (pinfunction "24_24") (pintype "passive"))
    )
    (net (code "133") (name "/H13") (class "Default")
      (node (ref "P1") (pin "H13") (pinfunction "LA07_P_H13") (pintype "passive"))
      (node (ref "P2") (pin "H13") (pinfunction "LA07_P_H13") (pintype "passive"))
      (node (ref "P4") (pin "26") (pinfunction "26_26") (pintype "passive"))
    )
    (net (code "134") (name "/H14") (class "Default")
      (node (ref "P1") (pin "H14") (pinfunction "LA07_N_H14") (pintype "passive"))
      (node (ref "P2") (pin "H14") (pinfunction "LA07_N_H14") (pintype "passive"))
      (node (ref "P4") (pin "28") (pinfunction "28_28") (pintype "passive"))
    )
    (net (code "135") (name "/H15") (class "Default")
      (node (ref "P1") (pin "H15") (pinfunction "GND_H15") (pintype "passive"))
      (node (ref "P2") (pin "H15") (pinfunction "GND_H15") (pintype "passive"))
      (node (ref "P4") (pin "30") (pinfunction "30_30") (pintype "passive"))
    )
    (net (code "136") (name "/H16") (class "Default")
      (node (ref "P1") (pin "H16") (pinfunction "LA11_P_H16") (pintype "passive"))
      (node (ref "P2") (pin "H16") (pinfunction "LA11_P_H16") (pintype "passive"))
      (node (ref "P4") (pin "32") (pinfunction "32_32") (pintype "passive"))
    )
    (net (code "137") (name "/H17") (class "Default")
      (node (ref "P1") (pin "H17") (pinfunction "LA11_N_H17") (pintype "passive"))
      (node (ref "P2") (pin "H17") (pinfunction "LA11_N_H17") (pintype "passive"))
      (node (ref "P4") (pin "34") (pinfunction "34_34") (pintype "passive"))
    )
    (net (code "138") (name "/H18") (class "Default")
      (node (ref "P1") (pin "H18") (pinfunction "GND_H18") (pintype "passive"))
      (node (ref "P2") (pin "H18") (pinfunction "GND_H18") (pintype "passive"))
      (node (ref "P4") (pin "36") (pinfunction "36_36") (pintype "passive"))
    )
    (net (code "139") (name "/H19") (class "Default")
      (node (ref "P1") (pin "H19") (pinfunction "LA15_P_H19") (pintype "passive"))
      (node (ref "P2") (pin "H19") (pinfunction "LA15_P_H19") (pintype "passive"))
      (node (ref "P4") (pin "38") (pinfunction "38_38") (pintype "passive"))
    )
    (net (code "140") (name "/H20") (class "Default")
      (node (ref "P1") (pin "H20") (pinfunction "LA15_N_H20") (pintype "passive"))
      (node (ref "P2") (pin "H20") (pinfunction "LA15_N_H20") (pintype "passive"))
      (node (ref "P4") (pin "40") (pinfunction "40_40") (pintype "passive"))
    )
    (net (code "141") (name "/H21") (class "Default")
      (node (ref "P1") (pin "H21") (pinfunction "GND_H21") (pintype "passive"))
      (node (ref "P2") (pin "H21") (pinfunction "GND_H21") (pintype "passive"))
      (node (ref "P4") (pin "42") (pinfunction "42_42") (pintype "passive"))
    )
    (net (code "142") (name "/H22") (class "Default")
      (node (ref "P1") (pin "H22") (pinfunction "LA19_P_H22") (pintype "passive"))
      (node (ref "P2") (pin "H22") (pinfunction "LA19_P_H22") (pintype "passive"))
      (node (ref "P4") (pin "44") (pinfunction "44_44") (pintype "passive"))
    )
    (net (code "143") (name "/H23") (class "Default")
      (node (ref "P1") (pin "H23") (pinfunction "LA19_N_H23") (pintype "passive"))
      (node (ref "P2") (pin "H23") (pinfunction "LA19_N_H23") (pintype "passive"))
      (node (ref "P4") (pin "46") (pinfunction "46_46") (pintype "passive"))
    )
    (net (code "144") (name "/H24") (class "Default")
      (node (ref "P1") (pin "H24") (pinfunction "GND_H24") (pintype "passive"))
      (node (ref "P2") (pin "H24") (pinfunction "GND_H24") (pintype "passive"))
      (node (ref "P4") (pin "48") (pinfunction "48_48") (pintype "passive"))
    )
    (net (code "145") (name "/H25") (class "Default")
      (node (ref "P1") (pin "H25") (pinfunction "LA21_P_H25") (pintype "passive"))
      (node (ref "P2") (pin "H25") (pinfunction "LA21_P_H25") (pintype "passive"))
      (node (ref "P4") (pin "50") (pinfunction "50_50") (pintype "passive"))
    )
    (net (code "146") (name "/H26") (class "Default")
      (node (ref "P1") (pin "H26") (pinfunction "LA21_N_H26") (pintype "passive"))
      (node (ref "P2") (pin "H26") (pinfunction "LA21_N_H26") (pintype "passive"))
      (node (ref "P4") (pin "52") (pinfunction "52_52") (pintype "passive"))
    )
    (net (code "147") (name "/H27") (class "Default")
      (node (ref "P1") (pin "H27") (pinfunction "GND_H27") (pintype "passive"))
      (node (ref "P2") (pin "H27") (pinfunction "GND_H27") (pintype "passive"))
      (node (ref "P4") (pin "54") (pinfunction "54_54") (pintype "passive"))
    )
    (net (code "148") (name "/H28") (class "Default")
      (node (ref "P1") (pin "H28") (pinfunction "LA24_P_H28") (pintype "passive"))
      (node (ref "P2") (pin "H28") (pinfunction "LA24_P_H28") (pintype "passive"))
      (node (ref "P4") (pin "56") (pinfunction "56_56") (pintype "passive"))
    )
    (net (code "149") (name "/H29") (class "Default")
      (node (ref "P1") (pin "H29") (pinfunction "LA24_N_H29") (pintype "passive"))
      (node (ref "P2") (pin "H29") (pinfunction "LA24_N_H29") (pintype "passive"))
      (node (ref "P4") (pin "58") (pinfunction "58_58") (pintype "passive"))
    )
    (net (code "150") (name "/H30") (class "Default")
      (node (ref "P1") (pin "H30") (pinfunction "GND_H30") (pintype "passive"))
      (node (ref "P2") (pin "H30") (pinfunction "GND_H30") (pintype "passive"))
      (node (ref "P4") (pin "60") (pinfunction "60_60") (pintype "passive"))
    )
    (net (code "151") (name "/H31") (class "Default")
      (node (ref "P1") (pin "H31") (pinfunction "LA28_P_H31") (pintype "passive"))
      (node (ref "P2") (pin "H31") (pinfunction "LA28_P_H31") (pintype "passive"))
      (node (ref "P4") (pin "62") (pinfunction "62_62") (pintype "passive"))
    )
    (net (code "152") (name "/H32") (class "Default")
      (node (ref "P1") (pin "H32") (pinfunction "LA28_N_H32") (pintype "passive"))
      (node (ref "P2") (pin "H32") (pinfunction "LA28_N_H32") (pintype "passive"))
      (node (ref "P4") (pin "64") (pinfunction "64_64") (pintype "passive"))
    )
    (net (code "153") (name "/H33") (class "Default")
      (node (ref "P1") (pin "H33") (pinfunction "GND_H33") (pintype "passive"))
      (node (ref "P2") (pin "H33") (pinfunction "GND_H33") (pintype "passive"))
      (node (ref "P4") (pin "66") (pinfunction "66_66") (pintype "passive"))
    )
    (net (code "154") (name "/H34") (class "Default")
      (node (ref "P1") (pin "H34") (pinfunction "LA30_P_H34") (pintype "passive"))
      (node (ref "P2") (pin "H34") (pinfunction "LA30_P_H34") (pintype "passive"))
      (node (ref "P4") (pin "68") (pinfunction "68_68") (pintype "passive"))
    )
    (net (code "155") (name "/H35") (class "Default")
      (node (ref "P1") (pin "H35") (pinfunction "LA30_N_H35") (pintype "passive"))
      (node (ref "P2") (pin "H35") (pinfunction "LA30_N_H35") (pintype "passive"))
      (node (ref "P4") (pin "70") (pinfunction "70_70") (pintype "passive"))
    )
    (net (code "156") (name "/H36") (class "Default")
      (node (ref "P1") (pin "H36") (pinfunction "GND_H36") (pintype "passive"))
      (node (ref "P2") (pin "H36") (pinfunction "GND_H36") (pintype "passive"))
      (node (ref "P4") (pin "72") (pinfunction "72_72") (pintype "passive"))
    )
    (net (code "157") (name "/H37") (class "Default")
      (node (ref "P1") (pin "H37") (pinfunction "LA32_P_H37") (pintype "passive"))
      (node (ref "P2") (pin "H37") (pinfunction "LA32_P_H37") (pintype "passive"))
      (node (ref "P4") (pin "74") (pinfunction "74_74") (pintype "passive"))
    )
    (net (code "158") (name "/H38") (class "Default")
      (node (ref "P1") (pin "H38") (pinfunction "LA32_N_H38") (pintype "passive"))
      (node (ref "P2") (pin "H38") (pinfunction "LA32_N_H38") (pintype "passive"))
      (node (ref "P4") (pin "76") (pinfunction "76_76") (pintype "passive"))
    )
    (net (code "159") (name "/H39") (class "Default")
      (node (ref "P1") (pin "H39") (pinfunction "GND_H39") (pintype "passive"))
      (node (ref "P2") (pin "H39") (pinfunction "GND_H39") (pintype "passive"))
      (node (ref "P4") (pin "78") (pinfunction "78_78") (pintype "passive"))
    )
    (net (code "160") (name "/H40") (class "Default")
      (node (ref "P1") (pin "H40") (pinfunction "VADJ_H40") (pintype "passive"))
      (node (ref "P2") (pin "H40") (pinfunction "VADJ_H40") (pintype "passive"))
      (node (ref "P4") (pin "80") (pinfunction "80_80") (pintype "passive"))
    )
    (net (code "161") (name "unconnected-(FM1-PadFD0)") (class "Default")
      (node (ref "FM1") (pin "FD0") (pinfunction "FD0_FD0") (pintype "passive"))
    )
    (net (code "162") (name "unconnected-(FM2-PadFD0)") (class "Default")
      (node (ref "FM2") (pin "FD0") (pinfunction "FD0_FD0") (pintype "passive"))
    )
    (net (code "163") (name "unconnected-(FM3-PadFD0)") (class "Default")
      (node (ref "FM3") (pin "FD0") (pinfunction "FD0_FD0") (pintype "passive"))
    )
    (net (code "164") (name "unconnected-(FM4-PadFD0)") (class "Default")
      (node (ref "FM4") (pin "FD0") (pinfunction "FD0_FD0") (pintype "passive"))
    )
    (net (code "165") (name "unconnected-(FM5-PadFD0)") (class "Default")
      (node (ref "FM5") (pin "FD0") (pinfunction "FD0_FD0") (pintype "passive"))
    )
    (net (code "166") (name "unconnected-(FM6-PadFD0)") (class "Default")
      (node (ref "FM6") (pin "FD0") (pinfunction "FD0_FD0") (pintype "passive"))
    )
    (net (code "167") (name "unconnected-(FM7-PadFD0)") (class "Default")
      (node (ref "FM7") (pin "FD0") (pinfunction "FD0_FD0") (pintype "passive"))
    )
    (net (code "168") (name "unconnected-(FM8-PadFD0)") (class "Default")
      (node (ref "FM8") (pin "FD0") (pinfunction "FD0_FD0") (pintype "passive"))
    )
    (net (code "169") (name "unconnected-(MH1-Pad0)") (class "Default")
      (node (ref "MH1") (pin "0") (pinfunction "0_0") (pintype "passive"))
    )
    (net (code "170") (name "unconnected-(MH2-Pad0)") (class "Default")
      (node (ref "MH2") (pin "0") (pinfunction "0_0") (pintype "passive"))
    )
    (net (code "171") (name "unconnected-(MH3-Pad0)") (class "Default")
      (node (ref "MH3") (pin "0") (pinfunction "0_0") (pintype "passive"))
    )
    (net (code "172") (name "unconnected-(MH4-Pad0)") (class "Default")
      (node (ref "MH4") (pin "0") (pinfunction "0_0") (pintype "passive"))
    )
  )
)
